# breakbeam-v1_1.net
KiCad netlist of a schematic drawn in EAGLE
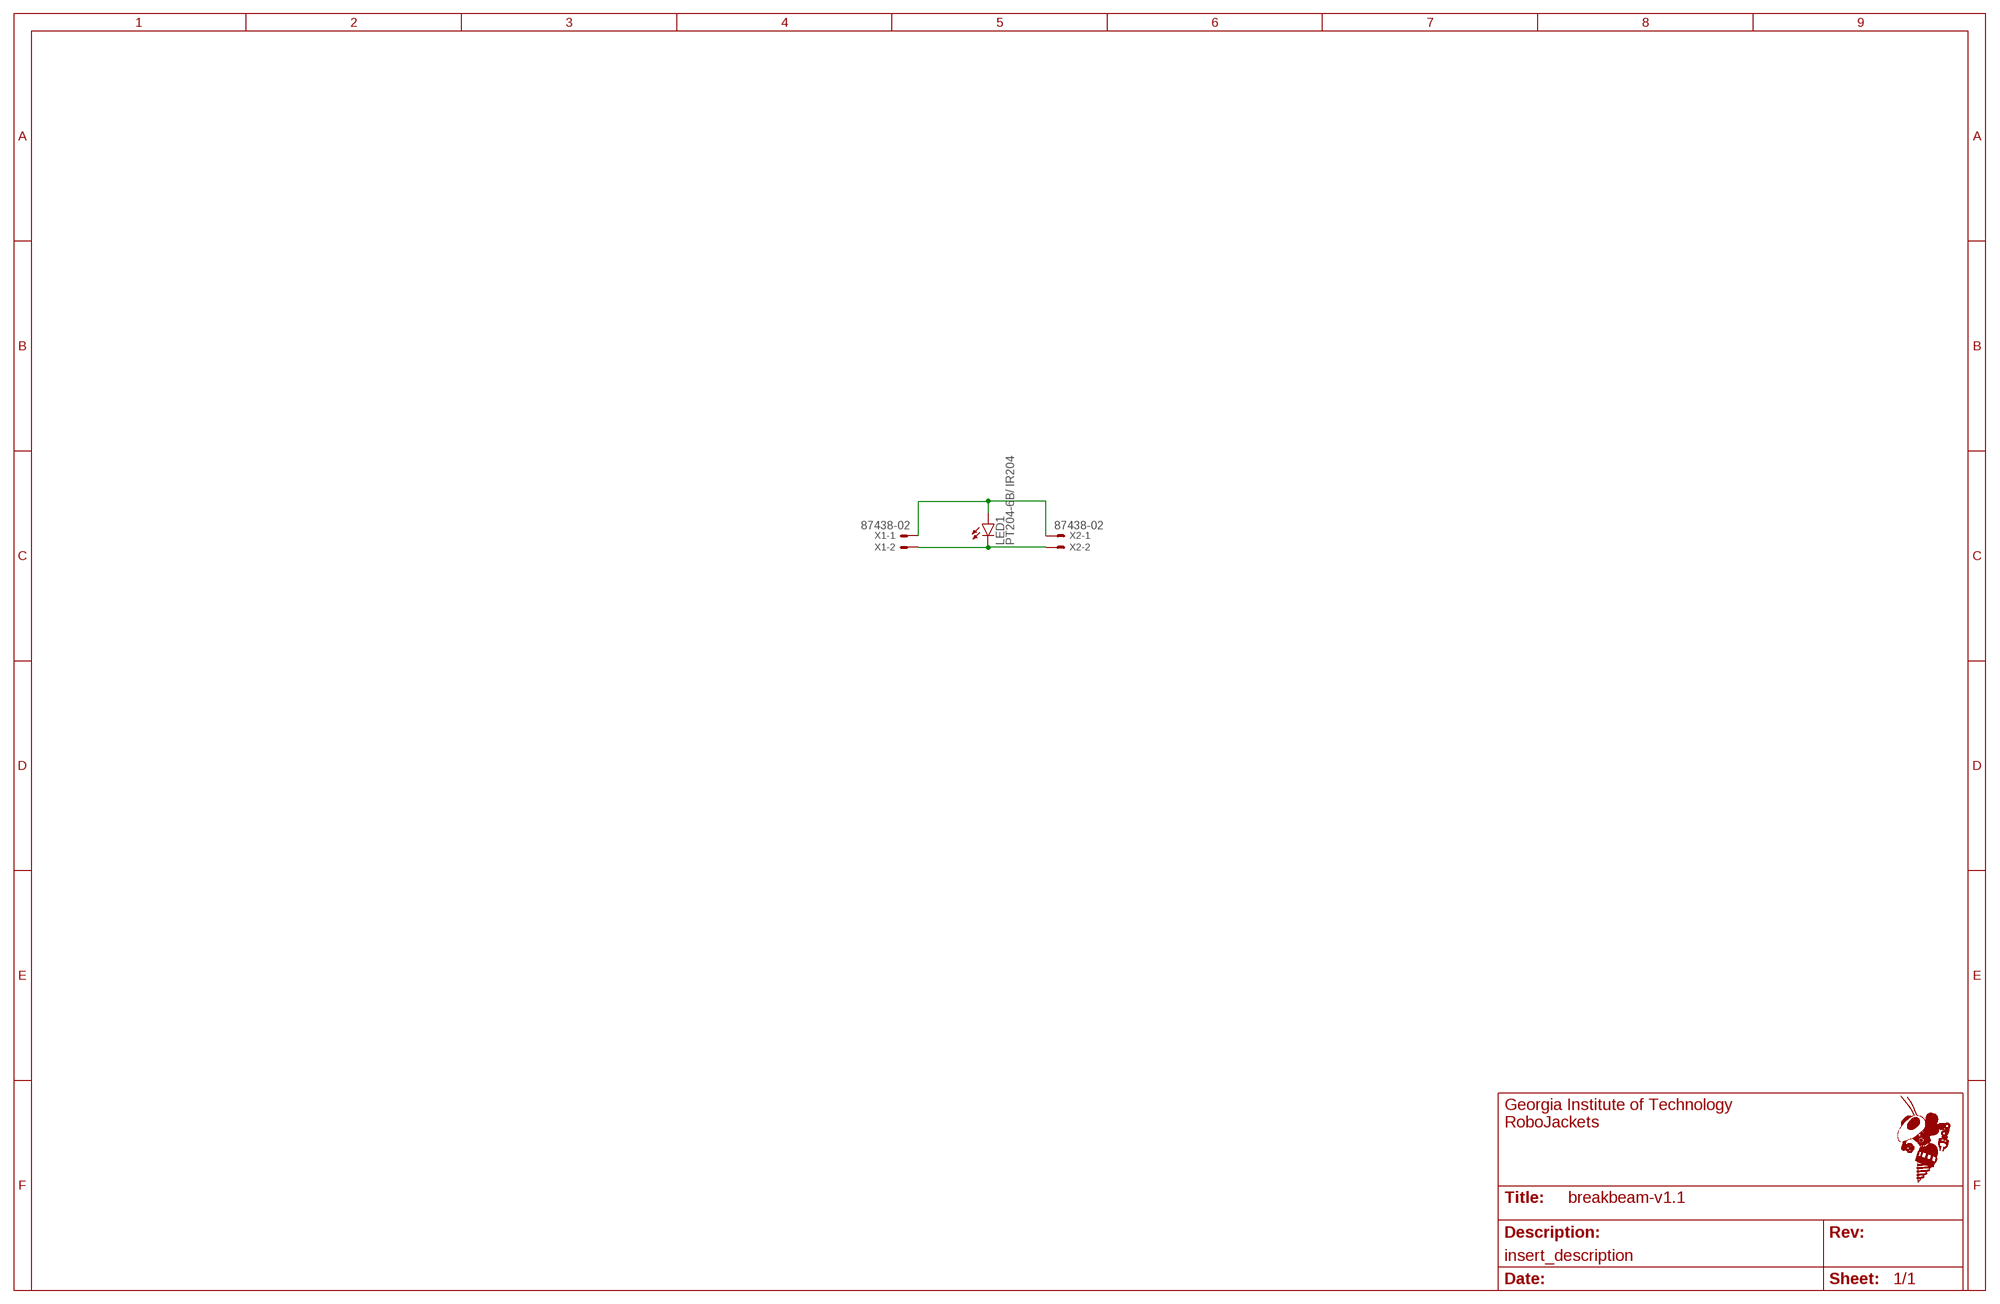
[diagram p0: schematic, sheet 1]

(export (version "E")
  (design (tool "Eeschema 10.0.6"))
  (components
    (comp (ref "LED1")
      (value "PT204-6B/ IR204")
      (footprint "eagle-import:LED3MM")
      (libsource (lib "eagle-import") (part "LED-THROUGHHOLE3MM"))
    )
    (comp (ref "X1")
      (value "87438-02")
      (footprint "eagle-import:87438-02")
      (fields (field (name "MF") "MOLEX"))
      (libsource (lib "eagle-import") (part "87438-02"))
    )
    (comp (ref "X2")
      (value "87438-02")
      (footprint "eagle-import:87438-02")
      (fields (field (name "MF") "MOLEX"))
      (libsource (lib "eagle-import") (part "87438-02"))
    )
  )
  (nets
    (net (code "1") (name "Net-(LED1-C)") (class "Default")
      (node (ref "LED1") (pin "K") (pinfunction "C_K") (pintype "passive"))
      (node (ref "X1") (pin "2") (pinfunction "S_2") (pintype "passive"))
      (node (ref "X2") (pin "2") (pinfunction "S_2") (pintype "passive"))
    )
    (net (code "2") (name "Net-(X1A-S)") (class "Default")
      (node (ref "LED1") (pin "A") (pinfunction "A_A") (pintype "passive"))
      (node (ref "X1") (pin "1") (pinfunction "S_1") (pintype "passive"))
      (node (ref "X2") (pin "1") (pinfunction "S_1") (pintype "passive"))
    )
  )
)
